# electrode.net
KiCad netlist of a schematic drawn in Altium Designer
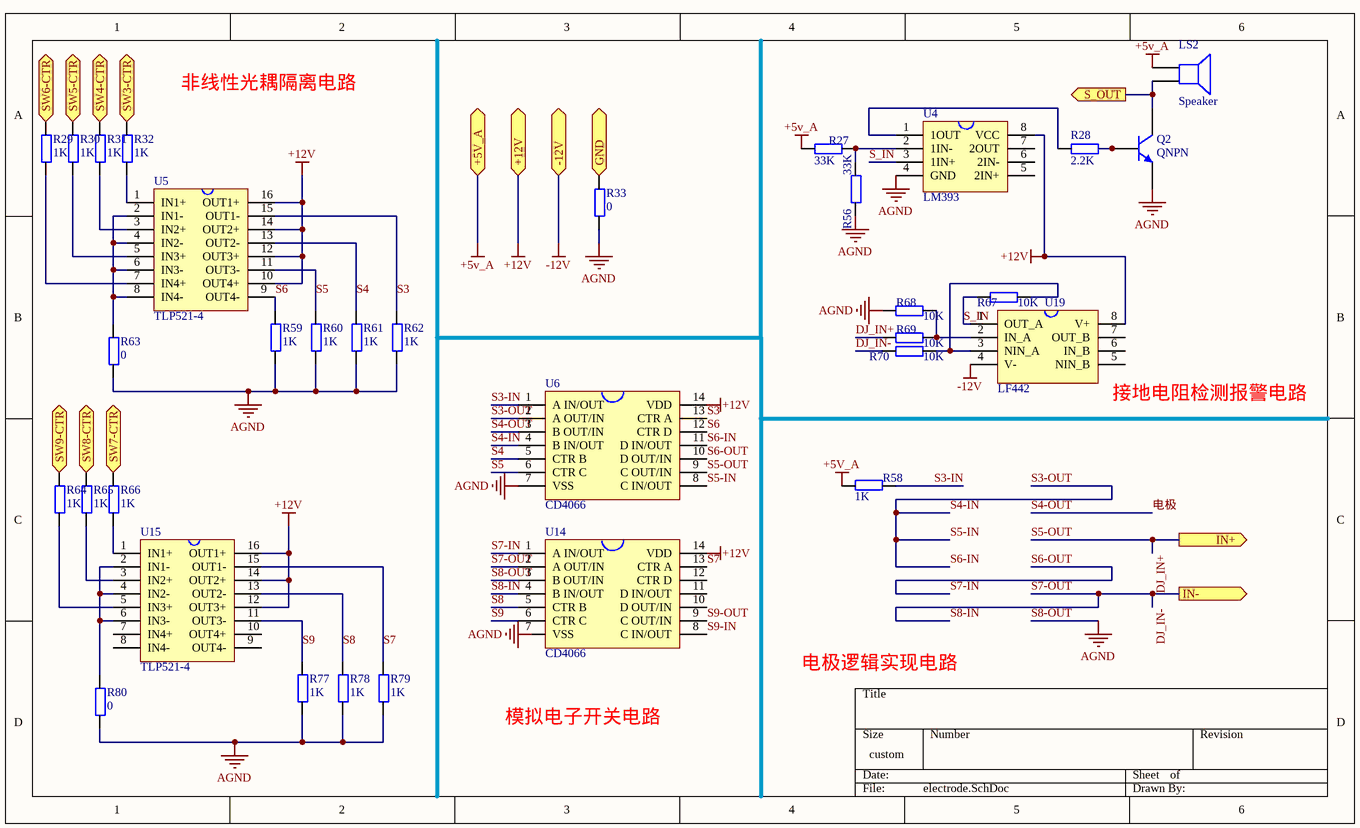
[diagram p0: electrode.SchDoc]

(export (version "E")
  (design (tool "Eeschema 10.0.6"))
  (components
    (comp (ref "LS2")
      (value "Speaker")
      (footprint "PIN2")
      (description "Loudspeaker")
      (fields (field (name "PUBLISHER") "Altium Limited"))
      (libsource (lib "Miscellaneous Devices") (part "Speaker"))
    )
    (comp (ref "Q2")
      (value "QNPN")
      (footprint "SOT-23B_N")
      (description "NPN Bipolar Transistor")
      (fields (field (name "PUBLISHER") "Altium Limited"))
      (libsource (lib "Miscellaneous Devices") (part "QNPN"))
    )
    (comp (ref "R27") (value "33K") (footprint "0603P") (libsource (lib "MiniSTM32 V3.0封装库") (part "R")))
    (comp (ref "R28") (value "2.2K") (footprint "0603P") (libsource (lib "MiniSTM32 V3.0封装库") (part "R")))
    (comp (ref "R29") (value "1K") (footprint "0603P") (libsource (lib "MiniSTM32 V3.0封装库") (part "R")))
    (comp (ref "R30") (value "1K") (footprint "0603P") (libsource (lib "MiniSTM32 V3.0封装库") (part "R")))
    (comp (ref "R31") (value "1K") (footprint "0603P") (libsource (lib "MiniSTM32 V3.0封装库") (part "R")))
    (comp (ref "R32") (value "1K") (footprint "0603P") (libsource (lib "MiniSTM32 V3.0封装库") (part "R")))
    (comp (ref "R33") (value "0") (footprint "0603P") (libsource (lib "MiniSTM32 V3.0封装库") (part "R")))
    (comp (ref "R56") (value "33K") (footprint "0603P") (libsource (lib "MiniSTM32 V3.0封装库") (part "R")))
    (comp (ref "R58") (value "1K") (footprint "0603P") (libsource (lib "MiniSTM32 V3.0封装库") (part "R")))
    (comp (ref "R59") (value "1K") (footprint "0603P") (libsource (lib "MiniSTM32 V3.0封装库") (part "R")))
    (comp (ref "R60") (value "1K") (footprint "0603P") (libsource (lib "MiniSTM32 V3.0封装库") (part "R")))
    (comp (ref "R61") (value "1K") (footprint "0603P") (libsource (lib "MiniSTM32 V3.0封装库") (part "R")))
    (comp (ref "R62") (value "1K") (footprint "0603P") (libsource (lib "MiniSTM32 V3.0封装库") (part "R")))
    (comp (ref "R63") (value "0") (footprint "0603P") (libsource (lib "MiniSTM32 V3.0封装库") (part "R")))
    (comp (ref "R64") (value "1K") (footprint "0603P") (libsource (lib "MiniSTM32 V3.0封装库") (part "R")))
    (comp (ref "R65") (value "1K") (footprint "0603P") (libsource (lib "MiniSTM32 V3.0封装库") (part "R")))
    (comp (ref "R66") (value "1K") (footprint "0603P") (libsource (lib "MiniSTM32 V3.0封装库") (part "R")))
    (comp (ref "R67") (value "10K") (footprint "0603P") (libsource (lib "MiniSTM32 V3.0封装库") (part "R")))
    (comp (ref "R68") (value "10K") (footprint "0603P") (libsource (lib "MiniSTM32 V3.0封装库") (part "R")))
    (comp (ref "R69") (value "10K") (footprint "0603P") (libsource (lib "MiniSTM32 V3.0封装库") (part "R")))
    (comp (ref "R70") (value "10K") (footprint "0603P") (libsource (lib "MiniSTM32 V3.0封装库") (part "R")))
    (comp (ref "R77") (value "1K") (footprint "0603P") (libsource (lib "MiniSTM32 V3.0封装库") (part "R")))
    (comp (ref "R78") (value "1K") (footprint "0603P") (libsource (lib "MiniSTM32 V3.0封装库") (part "R")))
    (comp (ref "R79") (value "1K") (footprint "0603P") (libsource (lib "MiniSTM32 V3.0封装库") (part "R")))
    (comp (ref "R80") (value "0") (footprint "0603P") (libsource (lib "MiniSTM32 V3.0封装库") (part "R")))
    (comp (ref "U4") (value "LM393") (footprint "R-PDSO-G8") (libsource (lib "dinafa") (part "LM393")))
    (comp (ref "U5") (value "TLP521-4") (footprint "11-20A3") (libsource (lib "dinafa") (part "TLP521")))
    (comp (ref "U6") (value "CD4066") (footprint "R-PDSO-G14") (libsource (lib "dinafa") (part "CD4066")))
    (comp (ref "U14") (value "CD4066") (footprint "R-PDSO-G14") (libsource (lib "dinafa") (part "CD4066")))
    (comp (ref "U15") (value "TLP521-4") (footprint "11-20A3") (libsource (lib "dinafa") (part "TLP521")))
    (comp (ref "U19") (value "LF442") (footprint "R-DIP-T8") (libsource (lib "dinafa") (part "LF442")))
  )
  (nets
    (net (code "1") (name "+5V_A") (class "Default")
      (node (ref "LS2") (pin "1") (pinfunction "1_1") (pintype "passive"))
      (node (ref "R27") (pin "1") (pintype "passive"))
      (node (ref "R58") (pin "2") (pintype "passive"))
    )
    (net (code "2") (name "+12V") (class "Default")
      (node (ref "U14") (pin "14") (pinfunction "VDD_14") (pintype "passive"))
      (node (ref "U15") (pin "12") (pinfunction "OUT3+_12") (pintype "passive"))
      (node (ref "U15") (pin "14") (pinfunction "OUT2+_14") (pintype "passive"))
      (node (ref "U15") (pin "16") (pinfunction "OUT1+_16") (pintype "passive"))
      (node (ref "U19") (pin "8") (pinfunction "V+_8") (pintype "passive"))
      (node (ref "U4") (pin "8") (pinfunction "VCC_8") (pintype "passive"))
      (node (ref "U5") (pin "10") (pinfunction "OUT4+_10") (pintype "passive"))
      (node (ref "U5") (pin "12") (pinfunction "OUT3+_12") (pintype "passive"))
      (node (ref "U5") (pin "14") (pinfunction "OUT2+_14") (pintype "passive"))
      (node (ref "U5") (pin "16") (pinfunction "OUT1+_16") (pintype "passive"))
      (node (ref "U6") (pin "14") (pinfunction "VDD_14") (pintype "passive"))
    )
    (net (code "3") (name "-12V") (class "Default")
      (node (ref "U19") (pin "4") (pinfunction "V-_4") (pintype "passive"))
    )
    (net (code "4") (name "/DJ_IN+") (class "Default")
      (node (ref "R69") (pin "1") (pintype "passive"))
      (node (ref "U6") (pin "9") (pinfunction "C_OUT/IN_9") (pintype "passive"))
    )
    (net (code "5") (name "/DJ_IN-") (class "Default")
      (node (ref "R70") (pin "1") (pintype "passive"))
      (node (ref "U14") (pin "2") (pinfunction "A_OUT/IN_2") (pintype "passive"))
      (node (ref "U14") (pin "4") (pinfunction "B_IN/OUT_4") (pintype "passive"))
    )
    (net (code "6") (name "/GND") (class "Default") (node (ref "R33") (pin "2") (pintype "passive")))
    (net (code "7") (name "/S3") (class "Default")
      (node (ref "R62") (pin "2") (pintype "passive"))
      (node (ref "U5") (pin "15") (pinfunction "OUT1-_15") (pintype "passive"))
      (node (ref "U6") (pin "13") (pinfunction "CTR_A_13") (pintype "passive"))
    )
    (net (code "8") (name "/S3-IN") (class "Default")
      (node (ref "R58") (pin "1") (pintype "passive"))
      (node (ref "U6") (pin "1") (pinfunction "A_IN/OUT_1") (pintype "passive"))
    )
    (net (code "9") (name "/S3-OUT") (class "Default")
      (node (ref "U6") (pin "11") (pinfunction "D_IN/OUT_11") (pintype "passive"))
      (node (ref "U6") (pin "2") (pinfunction "A_OUT/IN_2") (pintype "passive"))
      (node (ref "U6") (pin "4") (pinfunction "B_IN/OUT_4") (pintype "passive"))
      (node (ref "U6") (pin "8") (pinfunction "C_IN/OUT_8") (pintype "passive"))
    )
    (net (code "10") (name "/S4") (class "Default")
      (node (ref "R61") (pin "2") (pintype "passive"))
      (node (ref "U5") (pin "13") (pinfunction "OUT2-_13") (pintype "passive"))
      (node (ref "U6") (pin "5") (pinfunction "CTR_B_5") (pintype "passive"))
    )
    (net (code "11") (name "/S4-OUT") (class "Default")
      (node (ref "U6") (pin "3") (pinfunction "B_OUT/IN_3") (pintype "passive"))
    )
    (net (code "12") (name "/S5") (class "Default")
      (node (ref "R60") (pin "2") (pintype "passive"))
      (node (ref "U5") (pin "11") (pinfunction "OUT3-_11") (pintype "passive"))
      (node (ref "U6") (pin "6") (pinfunction "CTR_C_6") (pintype "passive"))
    )
    (net (code "13") (name "/S6") (class "Default")
      (node (ref "R59") (pin "2") (pintype "passive"))
      (node (ref "U5") (pin "9") (pinfunction "OUT4-_9") (pintype "passive"))
      (node (ref "U6") (pin "12") (pinfunction "CTR_D_12") (pintype "passive"))
    )
    (net (code "14") (name "/S6-OUT") (class "Default")
      (node (ref "U14") (pin "1") (pinfunction "A_IN/OUT_1") (pintype "passive"))
      (node (ref "U6") (pin "10") (pinfunction "D_OUT/IN_10") (pintype "passive"))
    )
    (net (code "15") (name "/S7") (class "Default")
      (node (ref "R79") (pin "2") (pintype "passive"))
      (node (ref "U14") (pin "13") (pinfunction "CTR_A_13") (pintype "passive"))
      (node (ref "U15") (pin "15") (pinfunction "OUT1-_15") (pintype "passive"))
    )
    (net (code "16") (name "/S8") (class "Default")
      (node (ref "R78") (pin "2") (pintype "passive"))
      (node (ref "U14") (pin "5") (pinfunction "CTR_B_5") (pintype "passive"))
      (node (ref "U15") (pin "13") (pinfunction "OUT2-_13") (pintype "passive"))
    )
    (net (code "17") (name "/S9") (class "Default")
      (node (ref "R77") (pin "2") (pintype "passive"))
      (node (ref "U14") (pin "6") (pinfunction "CTR_C_6") (pintype "passive"))
      (node (ref "U15") (pin "11") (pinfunction "OUT3-_11") (pintype "passive"))
    )
    (net (code "18") (name "/S9-IN") (class "Default")
      (node (ref "U14") (pin "8") (pinfunction "C_IN/OUT_8") (pintype "passive"))
    )
    (net (code "19") (name "/S9-OUT") (class "Default")
      (node (ref "U14") (pin "9") (pinfunction "C_OUT/IN_9") (pintype "passive"))
    )
    (net (code "20") (name "/SW3-CTR") (class "Default") (node (ref "R32") (pin "2") (pintype "passive")))
    (net (code "21") (name "/SW4-CTR") (class "Default") (node (ref "R31") (pin "2") (pintype "passive")))
    (net (code "22") (name "/SW5-CTR") (class "Default") (node (ref "R30") (pin "2") (pintype "passive")))
    (net (code "23") (name "/SW6-CTR") (class "Default") (node (ref "R29") (pin "2") (pintype "passive")))
    (net (code "24") (name "/SW7-CTR") (class "Default") (node (ref "R66") (pin "2") (pintype "passive")))
    (net (code "25") (name "/SW8-CTR") (class "Default") (node (ref "R65") (pin "2") (pintype "passive")))
    (net (code "26") (name "/SW9-CTR") (class "Default") (node (ref "R64") (pin "2") (pintype "passive")))
    (net (code "27") (name "/S_IN") (class "Default")
      (node (ref "R67") (pin "1") (pintype "passive"))
      (node (ref "U19") (pin "1") (pinfunction "OUT_A_1") (pintype "passive"))
      (node (ref "U4") (pin "3") (pinfunction "1IN+_3") (pintype "passive"))
    )
    (net (code "28") (name "/S_OUT") (class "Default")
      (node (ref "LS2") (pin "2") (pinfunction "2_2") (pintype "passive"))
      (node (ref "Q2") (pin "1") (pinfunction "C_1") (pintype "passive"))
    )
    (net (code "29") (name "AGND") (class "Default")
      (node (ref "Q2") (pin "3") (pinfunction "E_3") (pintype "passive"))
      (node (ref "R33") (pin "1") (pintype "passive"))
      (node (ref "R56") (pin "1") (pintype "passive"))
      (node (ref "R59") (pin "1") (pintype "passive"))
      (node (ref "R60") (pin "1") (pintype "passive"))
      (node (ref "R61") (pin "1") (pintype "passive"))
      (node (ref "R62") (pin "1") (pintype "passive"))
      (node (ref "R63") (pin "1") (pintype "passive"))
      (node (ref "R68") (pin "1") (pintype "passive"))
      (node (ref "R77") (pin "1") (pintype "passive"))
      (node (ref "R78") (pin "1") (pintype "passive"))
      (node (ref "R79") (pin "1") (pintype "passive"))
      (node (ref "R80") (pin "1") (pintype "passive"))
      (node (ref "U14") (pin "3") (pinfunction "B_OUT/IN_3") (pintype "passive"))
      (node (ref "U4") (pin "4") (pinfunction "GND_4") (pintype "passive"))
      (node (ref "U6") (pin "7") (pinfunction "VSS_7") (pintype "passive"))
    )
    (net (code "30") (name "Net-(Q2-B)") (class "Default")
      (node (ref "Q2") (pin "2") (pinfunction "B_2") (pintype "passive"))
      (node (ref "R28") (pin "2") (pintype "passive"))
    )
    (net (code "31") (name "Net-(U4-1IN-)") (class "Default")
      (node (ref "R27") (pin "2") (pintype "passive"))
      (node (ref "R56") (pin "2") (pintype "passive"))
      (node (ref "U4") (pin "2") (pinfunction "1IN-_2") (pintype "passive"))
    )
    (net (code "32") (name "Net-(U4-1OUT)") (class "Default")
      (node (ref "R28") (pin "1") (pintype "passive"))
      (node (ref "U4") (pin "1") (pinfunction "1OUT_1") (pintype "passive"))
    )
    (net (code "33") (name "Net-(U5-IN1+)") (class "Default")
      (node (ref "R32") (pin "1") (pintype "passive"))
      (node (ref "U5") (pin "1") (pinfunction "IN1+_1") (pintype "passive"))
    )
    (net (code "34") (name "Net-(U5-IN1-)") (class "Default")
      (node (ref "R63") (pin "2") (pintype "passive"))
      (node (ref "U5") (pin "2") (pinfunction "IN1-_2") (pintype "passive"))
      (node (ref "U5") (pin "4") (pinfunction "IN2-_4") (pintype "passive"))
      (node (ref "U5") (pin "6") (pinfunction "IN3-_6") (pintype "passive"))
      (node (ref "U5") (pin "8") (pinfunction "IN4-_8") (pintype "passive"))
    )
    (net (code "35") (name "Net-(U5-IN2+)") (class "Default")
      (node (ref "R31") (pin "1") (pintype "passive"))
      (node (ref "U5") (pin "3") (pinfunction "IN2+_3") (pintype "passive"))
    )
    (net (code "36") (name "Net-(U5-IN3+)") (class "Default")
      (node (ref "R30") (pin "1") (pintype "passive"))
      (node (ref "U5") (pin "5") (pinfunction "IN3+_5") (pintype "passive"))
    )
    (net (code "37") (name "Net-(U5-IN4+)") (class "Default")
      (node (ref "R29") (pin "1") (pintype "passive"))
      (node (ref "U5") (pin "7") (pinfunction "IN4+_7") (pintype "passive"))
    )
    (net (code "38") (name "Net-(U15-IN1+)") (class "Default")
      (node (ref "R66") (pin "1") (pintype "passive"))
      (node (ref "U15") (pin "1") (pinfunction "IN1+_1") (pintype "passive"))
    )
    (net (code "39") (name "Net-(U15-IN1-)") (class "Default")
      (node (ref "R80") (pin "2") (pintype "passive"))
      (node (ref "U15") (pin "2") (pinfunction "IN1-_2") (pintype "passive"))
      (node (ref "U15") (pin "4") (pinfunction "IN2-_4") (pintype "passive"))
      (node (ref "U15") (pin "6") (pinfunction "IN3-_6") (pintype "passive"))
    )
    (net (code "40") (name "Net-(U15-IN2+)") (class "Default")
      (node (ref "R65") (pin "1") (pintype "passive"))
      (node (ref "U15") (pin "3") (pinfunction "IN2+_3") (pintype "passive"))
    )
    (net (code "41") (name "Net-(U15-IN3+)") (class "Default")
      (node (ref "R64") (pin "1") (pintype "passive"))
      (node (ref "U15") (pin "5") (pinfunction "IN3+_5") (pintype "passive"))
    )
    (net (code "42") (name "Net-(U19-IN_A)") (class "Default")
      (node (ref "R68") (pin "2") (pintype "passive"))
      (node (ref "R69") (pin "2") (pintype "passive"))
      (node (ref "U19") (pin "2") (pinfunction "IN_A_2") (pintype "passive"))
    )
    (net (code "43") (name "Net-(U19-NIN_A)") (class "Default")
      (node (ref "R67") (pin "2") (pintype "passive"))
      (node (ref "R70") (pin "2") (pintype "passive"))
      (node (ref "U19") (pin "3") (pinfunction "NIN_A_3") (pintype "passive"))
    )
    (net (code "44") (name "unconnected-(U4-2IN+-Pad5)") (class "Default")
      (node (ref "U4") (pin "5") (pinfunction "2IN+_5") (pintype "passive"))
    )
    (net (code "45") (name "unconnected-(U4-2IN--Pad6)") (class "Default")
      (node (ref "U4") (pin "6") (pinfunction "2IN-_6") (pintype "passive"))
    )
    (net (code "46") (name "unconnected-(U4-2OUT-Pad7)") (class "Default")
      (node (ref "U4") (pin "7") (pinfunction "2OUT_7") (pintype "passive"))
    )
    (net (code "47") (name "unconnected-(U14-CTR_D-Pad12)") (class "Default")
      (node (ref "U14") (pin "12") (pinfunction "CTR_D_12") (pintype "passive"))
    )
    (net (code "48") (name "unconnected-(U14-D_IN{slash}OUT-Pad11)") (class "Default")
      (node (ref "U14") (pin "11") (pinfunction "D_IN/OUT_11") (pintype "passive"))
    )
    (net (code "49") (name "unconnected-(U14-D_OUT{slash}IN-Pad10)") (class "Default")
      (node (ref "U14") (pin "10") (pinfunction "D_OUT/IN_10") (pintype "passive"))
    )
    (net (code "50") (name "unconnected-(U14-VSS-Pad7)") (class "Default")
      (node (ref "U14") (pin "7") (pinfunction "VSS_7") (pintype "passive"))
    )
    (net (code "51") (name "unconnected-(U15-IN4+-Pad7)") (class "Default")
      (node (ref "U15") (pin "7") (pinfunction "IN4+_7") (pintype "passive"))
    )
    (net (code "52") (name "unconnected-(U15-IN4--Pad8)") (class "Default")
      (node (ref "U15") (pin "8") (pinfunction "IN4-_8") (pintype "passive"))
    )
    (net (code "53") (name "unconnected-(U15-OUT4+-Pad10)") (class "Default")
      (node (ref "U15") (pin "10") (pinfunction "OUT4+_10") (pintype "passive"))
    )
    (net (code "54") (name "unconnected-(U15-OUT4--Pad9)") (class "Default")
      (node (ref "U15") (pin "9") (pinfunction "OUT4-_9") (pintype "passive"))
    )
    (net (code "55") (name "unconnected-(U19-IN_B-Pad6)") (class "Default")
      (node (ref "U19") (pin "6") (pinfunction "IN_B_6") (pintype "passive"))
    )
    (net (code "56") (name "unconnected-(U19-NIN_B-Pad5)") (class "Default")
      (node (ref "U19") (pin "5") (pinfunction "NIN_B_5") (pintype "passive"))
    )
    (net (code "57") (name "unconnected-(U19-OUT_B-Pad7)") (class "Default")
      (node (ref "U19") (pin "7") (pinfunction "OUT_B_7") (pintype "passive"))
    )
  )
)
